# RES_IN24.net
KiCad netlist of a schematic drawn in Altium Designer
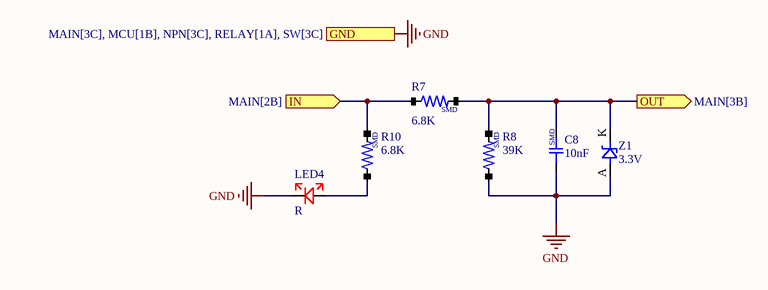
[diagram p0: RES_IN24.SchDoc]

(export (version "E")
  (design (tool "Eeschema 10.0.6"))
  (components
    (comp (ref "C8") (value "10nF") (footprint "CAP-0603") (libsource (lib "kave-eng-pro") (part "cap_smd")))
    (comp (ref "LED4")
      (value "R")
      (footprint "LED/0805")
      (libsource (lib "kave-eng-pro") (part "LED-1COLER"))
    )
    (comp (ref "R7") (value "6.8K") (footprint "RES/0805") (libsource (lib "") (part "RES/SMD_1")))
    (comp (ref "R8") (value "39K") (footprint "RES/0805") (libsource (lib "kave-eng-pro") (part "RES/SMD")))
    (comp (ref "R10") (value "6.8K") (footprint "RES/0805") (libsource (lib "kave-eng-pro") (part "RES/SMD")))
    (comp (ref "Z1")
      (value "3.3V")
      (footprint "mini_melf")
      (libsource (lib "kave-eng-pro") (part "zener-0.5w"))
    )
  )
  (nets
    (net (code "1") (name "/IN") (class "Default")
      (node (ref "R10") (pin "2") (pinfunction "2_2") (pintype "passive"))
      (node (ref "R7") (pin "1") (pinfunction "1_1") (pintype "passive"))
    )
    (net (code "2") (name "/OUT") (class "Default")
      (node (ref "C8") (pin "2") (pintype "passive"))
      (node (ref "R7") (pin "2") (pinfunction "2_2") (pintype "passive"))
      (node (ref "R8") (pin "2") (pinfunction "2_2") (pintype "passive"))
      (node (ref "Z1") (pin "K") (pintype "passive"))
    )
    (net (code "3") (name "GND") (class "Default")
      (node (ref "C8") (pin "1") (pintype "passive"))
      (node (ref "LED4") (pin "K") (pintype "passive"))
      (node (ref "R8") (pin "1") (pinfunction "1_1") (pintype "passive"))
      (node (ref "Z1") (pin "A") (pintype "passive"))
    )
    (net (code "4") (name "Net-(LED4-PadA)") (class "Default")
      (node (ref "LED4") (pin "A") (pintype "passive"))
      (node (ref "R10") (pin "1") (pinfunction "1_1") (pintype "passive"))
    )
  )
)
